# SECUREBRD_002.net
KiCad netlist of a schematic drawn in EAGLE
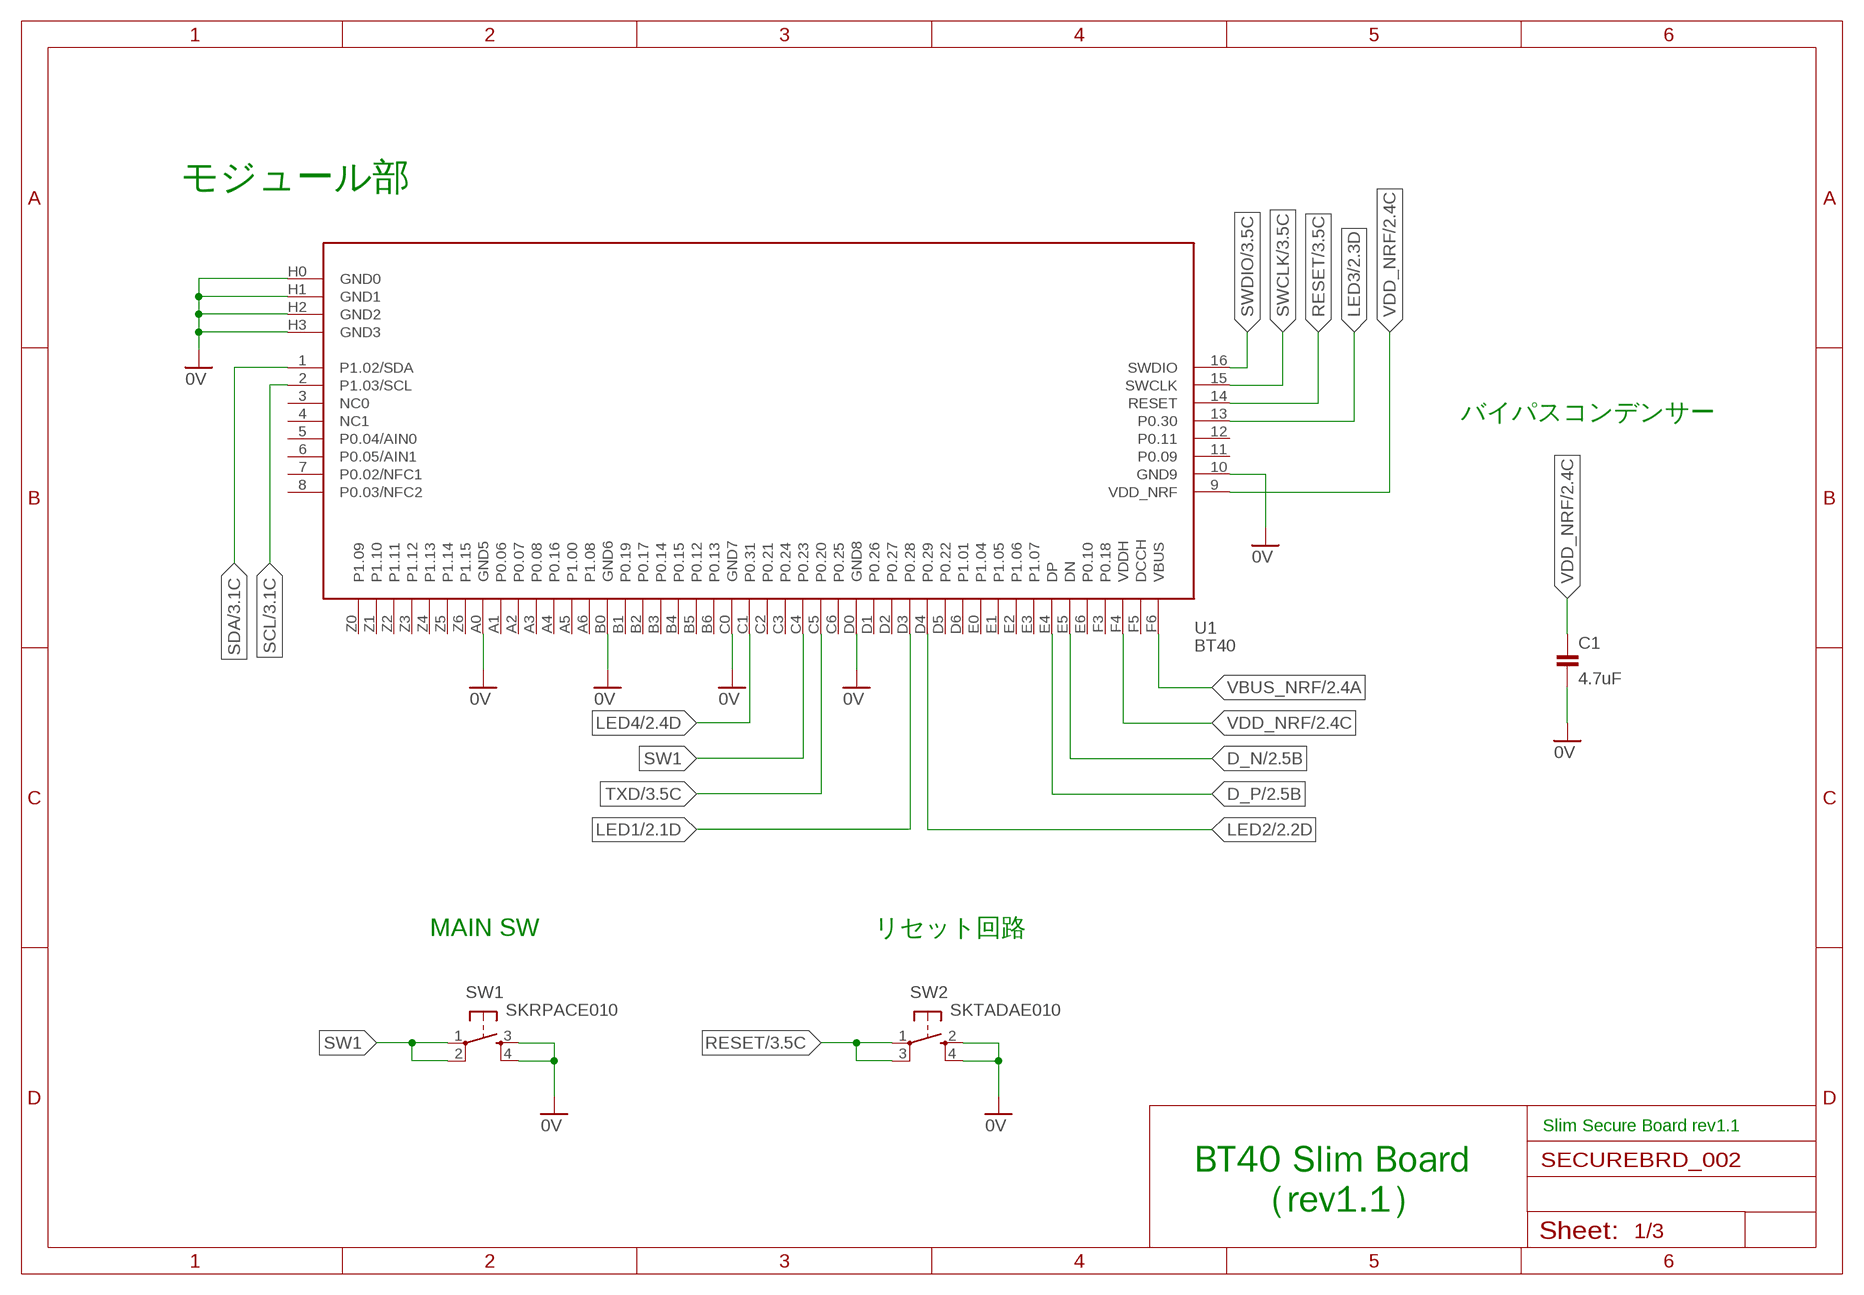
[diagram p0: schematic, sheet 1]
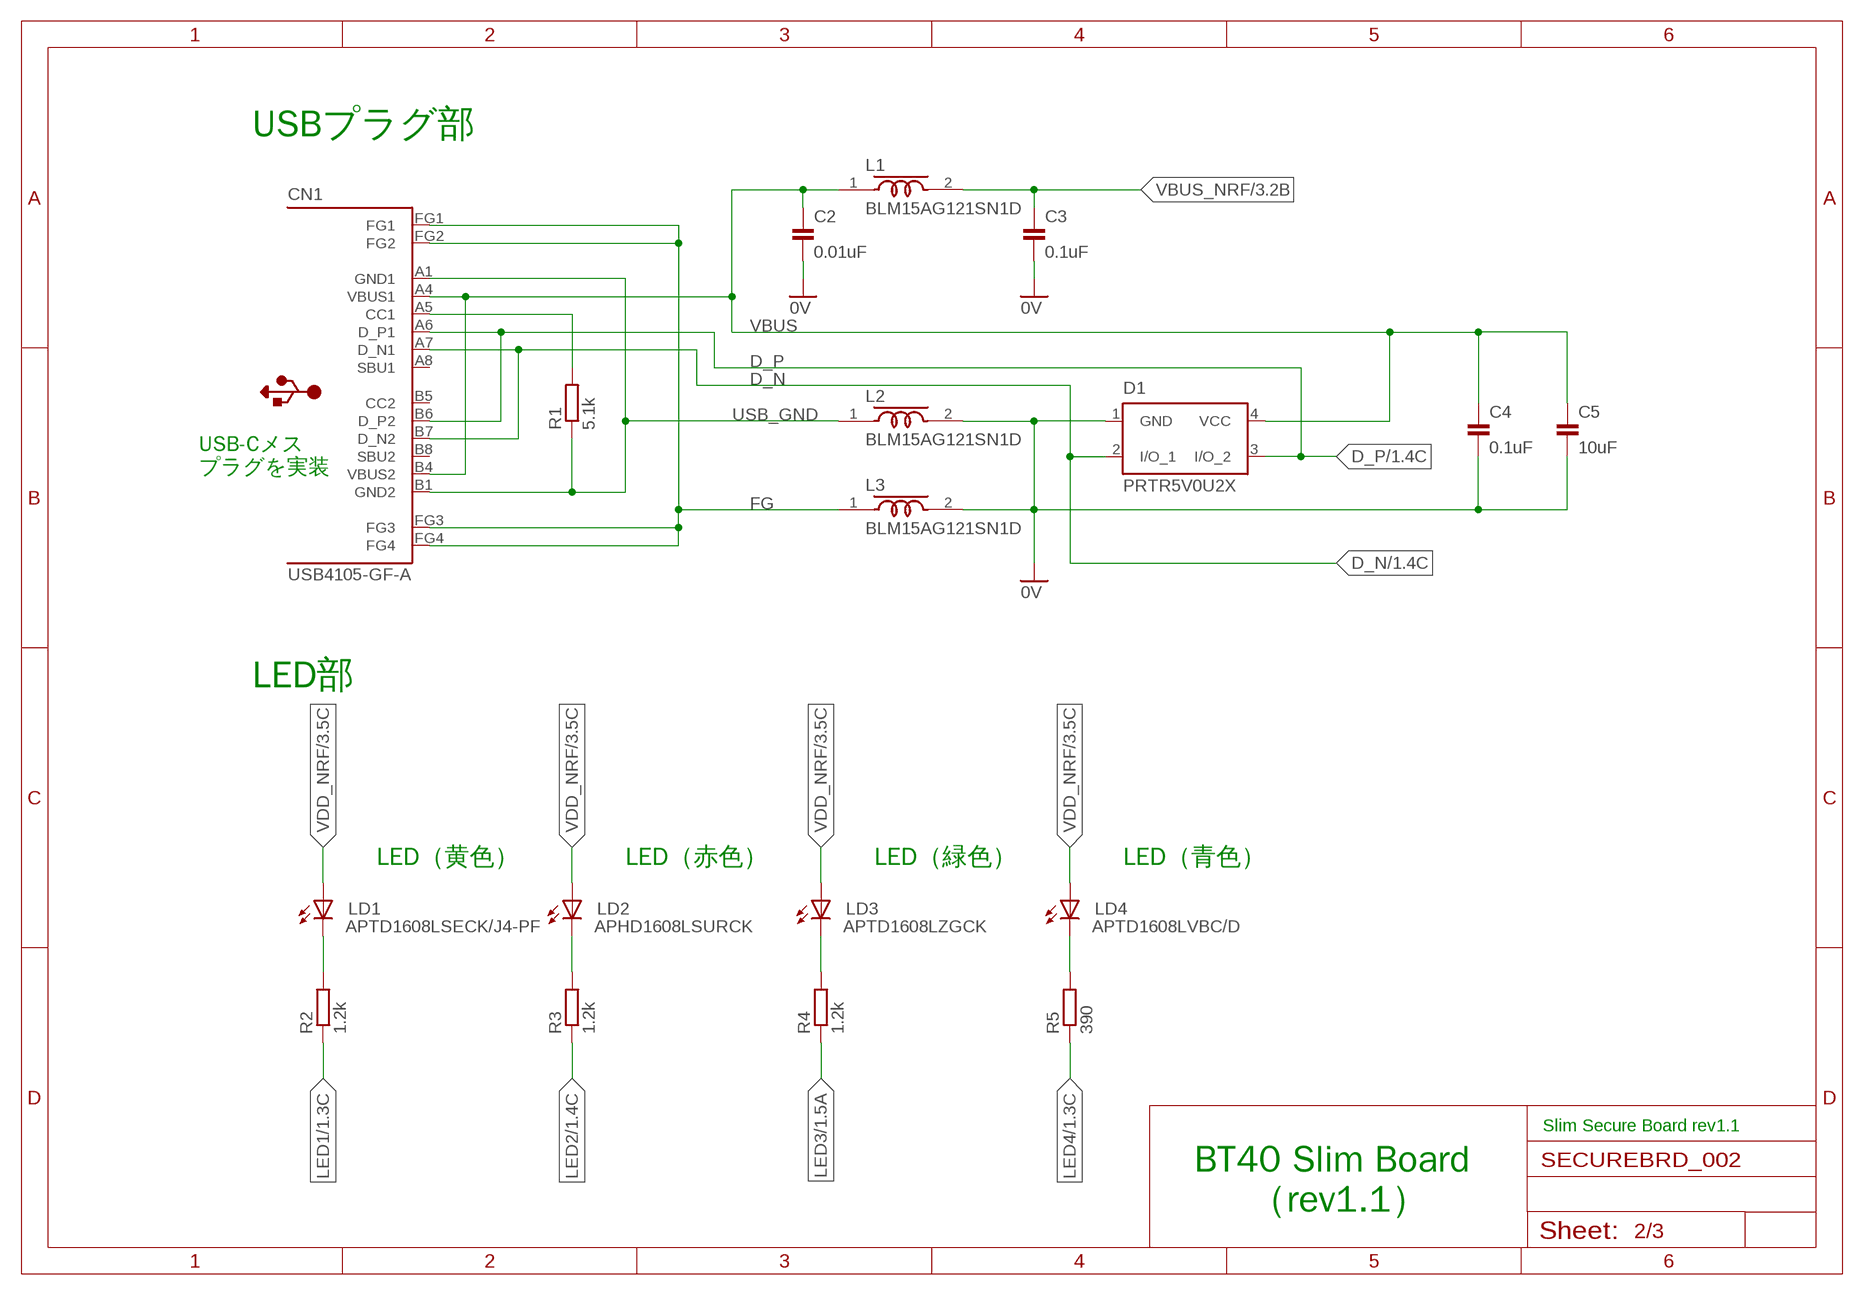
[diagram p1: schematic, sheet 2]
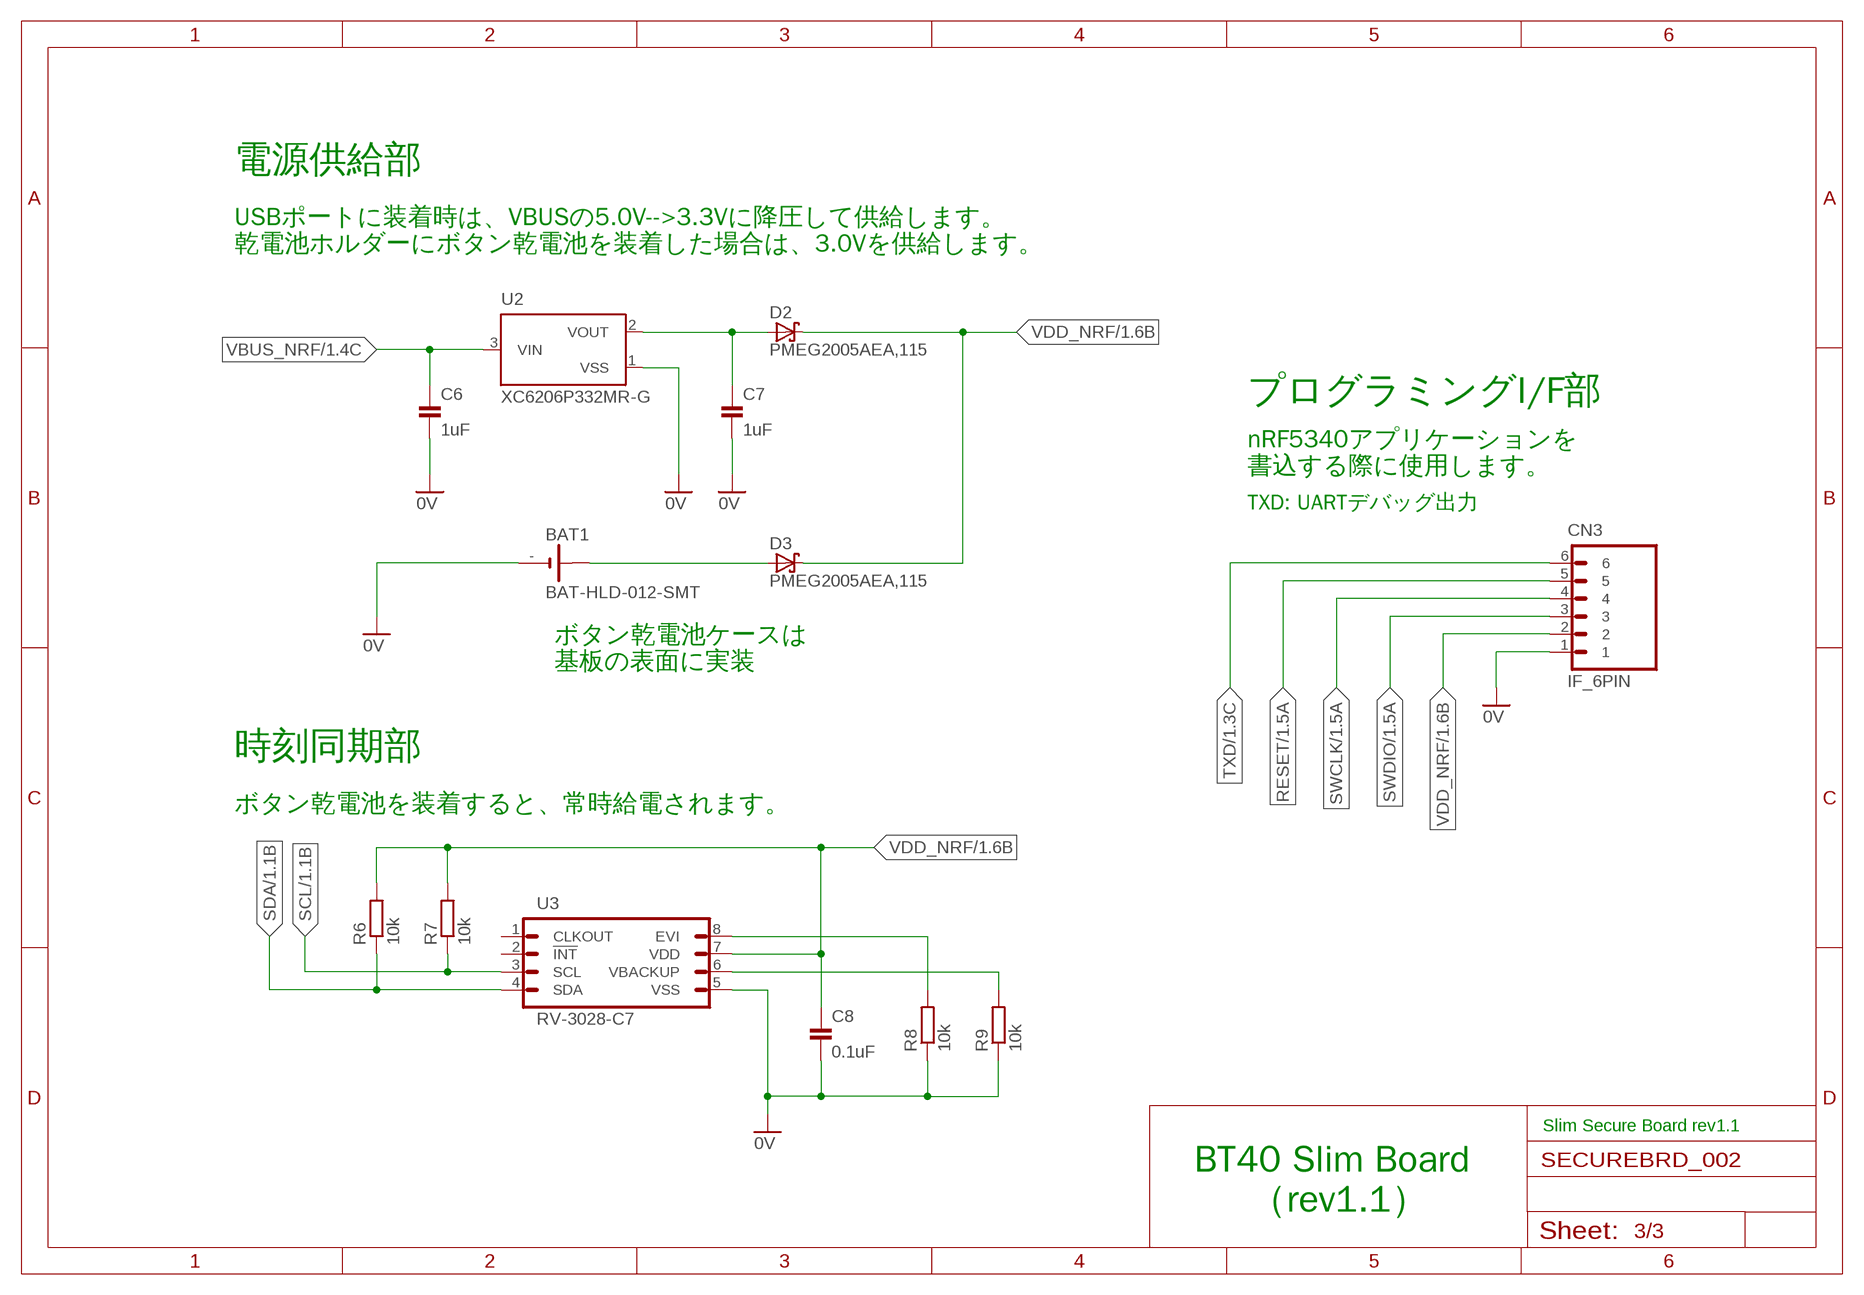
[diagram p2: schematic, sheet 3]

(export (version "E")
  (design (tool "Eeschema 10.0.6"))
  (components
    (comp (ref "C1")
      (value "4.7uF")
      (footprint "eagle-import:C0603K")
      (libsource (lib "eagle-import") (part "CAP_0603"))
    )
    (comp (ref "SW1")
      (value "SKRPACE010")
      (footprint "eagle-import:SKRPACE010")
      (libsource (lib "eagle-import") (part "SKRPACE010"))
    )
    (comp (ref "SW2")
      (value "SKTADAE010")
      (footprint "eagle-import:SKTADAE010")
      (libsource (lib "eagle-import") (part "SKTADAE010"))
    )
    (comp (ref "U1")
      (value "BT40")
      (footprint "eagle-import:BM40-B_1PRIMARY")
      (libsource (lib "eagle-import") (part "BT40"))
    )
    (comp (ref "C2")
      (value "0.01uF")
      (footprint "eagle-import:C0402K")
      (libsource (lib "eagle-import") (part "CAP_0402K"))
    )
    (comp (ref "C3")
      (value "0.1uF")
      (footprint "eagle-import:C0402K")
      (libsource (lib "eagle-import") (part "CAP_0402K"))
    )
    (comp (ref "C4")
      (value "0.1uF")
      (footprint "eagle-import:C0402K")
      (libsource (lib "eagle-import") (part "CAP_0402K"))
    )
    (comp (ref "C5")
      (value "10uF")
      (footprint "eagle-import:C0603K")
      (libsource (lib "eagle-import") (part "CAP_0603"))
    )
    (comp (ref "CN1")
      (value "USB4105-GF-A")
      (footprint "eagle-import:USB4105-GF-A")
      (libsource (lib "eagle-import") (part "USB4105-GF-A"))
    )
    (comp (ref "D1")
      (value "PRTR5V0U2X")
      (footprint "eagle-import:SOT143B")
      (libsource (lib "eagle-import") (part "PRTR5V0U2X"))
    )
    (comp (ref "L1")
      (value "BLM15AG121SN1D")
      (footprint "eagle-import:C0402K")
      (libsource (lib "eagle-import") (part "BLM15AG121SN1D"))
    )
    (comp (ref "L2")
      (value "BLM15AG121SN1D")
      (footprint "eagle-import:C0402K")
      (libsource (lib "eagle-import") (part "BLM15AG121SN1D"))
    )
    (comp (ref "L3")
      (value "BLM15AG121SN1D")
      (footprint "eagle-import:C0402K")
      (libsource (lib "eagle-import") (part "BLM15AG121SN1D"))
    )
    (comp (ref "LD1")
      (value "APTD1608LSECK/J4-PF")
      (footprint "eagle-import:APTD1608")
      (libsource (lib "eagle-import") (part "APTD1608LSECK/J4-PF"))
    )
    (comp (ref "LD2")
      (value "APHD1608LSURCK")
      (footprint "eagle-import:APTD1608")
      (libsource (lib "eagle-import") (part "APHD1608LSURCK"))
    )
    (comp (ref "LD3")
      (value "APTD1608LZGCK")
      (footprint "eagle-import:APTD1608")
      (libsource (lib "eagle-import") (part "APTD1608LZGCK"))
    )
    (comp (ref "LD4")
      (value "APTD1608LVBC/D")
      (footprint "eagle-import:APTD1608")
      (libsource (lib "eagle-import") (part "APTD1608LVBC/D"))
    )
    (comp (ref "R1")
      (value "5.1k")
      (footprint "eagle-import:R0402")
      (libsource (lib "eagle-import") (part "RESISTOR_0402"))
    )
    (comp (ref "R2")
      (value "1.2k")
      (footprint "eagle-import:R0402")
      (libsource (lib "eagle-import") (part "RESISTOR_0402"))
    )
    (comp (ref "R3")
      (value "1.2k")
      (footprint "eagle-import:R0402")
      (libsource (lib "eagle-import") (part "RESISTOR_0402"))
    )
    (comp (ref "R4")
      (value "1.2k")
      (footprint "eagle-import:R0402")
      (libsource (lib "eagle-import") (part "RESISTOR_0402"))
    )
    (comp (ref "R5")
      (value "390")
      (footprint "eagle-import:R0402")
      (libsource (lib "eagle-import") (part "RESISTOR_0402"))
    )
    (comp (ref "BAT1")
      (value "BAT-HLD-012-SMT")
      (footprint "eagle-import:BAT-HLD-012-SMT")
      (libsource (lib "eagle-import") (part "BAT-HLD-012-SMT"))
    )
    (comp (ref "C6")
      (value "1uF")
      (footprint "eagle-import:C0603K")
      (libsource (lib "eagle-import") (part "CAP_0603"))
    )
    (comp (ref "C7")
      (value "1uF")
      (footprint "eagle-import:C0603K")
      (libsource (lib "eagle-import") (part "CAP_0603"))
    )
    (comp (ref "C8")
      (value "0.1uF")
      (footprint "eagle-import:C0402K")
      (libsource (lib "eagle-import") (part "CAP_0402K"))
    )
    (comp (ref "CN3")
      (value "IF_6PIN")
      (footprint "eagle-import:HEADER_6PIN")
      (libsource (lib "eagle-import") (part "IF_6PIN"))
    )
    (comp (ref "D2")
      (value "PMEG2005AEA,115")
      (footprint "eagle-import:SOD323-W")
      (libsource (lib "eagle-import") (part "PMEG2005AEA,115"))
    )
    (comp (ref "D3")
      (value "PMEG2005AEA,115")
      (footprint "eagle-import:SOD323-W")
      (libsource (lib "eagle-import") (part "PMEG2005AEA,115"))
    )
    (comp (ref "R6")
      (value "10k")
      (footprint "eagle-import:R0402")
      (libsource (lib "eagle-import") (part "RESISTOR_0402"))
    )
    (comp (ref "R7")
      (value "10k")
      (footprint "eagle-import:R0402")
      (libsource (lib "eagle-import") (part "RESISTOR_0402"))
    )
    (comp (ref "R8")
      (value "10k")
      (footprint "eagle-import:R0402")
      (libsource (lib "eagle-import") (part "RESISTOR_0402"))
    )
    (comp (ref "R9")
      (value "10k")
      (footprint "eagle-import:R0402")
      (libsource (lib "eagle-import") (part "RESISTOR_0402"))
    )
    (comp (ref "U2")
      (value "XC6206P332MR-G")
      (footprint "eagle-import:SOT23")
      (libsource (lib "eagle-import") (part "XC6206P332MR-G"))
    )
    (comp (ref "U3")
      (value "RV-3028-C7")
      (footprint "eagle-import:SON-8")
      (libsource (lib "eagle-import") (part "RV-3028-C7"))
    )
  )
  (nets
    (net (code "1") (name "0V") (class "Default")
      (node (ref "BAT1") (pin "-") (pinfunction "-_-") (pintype "passive"))
      (node (ref "C1") (pin "2") (pinfunction "2_2") (pintype "passive"))
      (node (ref "C2") (pin "2") (pinfunction "2_2") (pintype "passive"))
      (node (ref "C3") (pin "2") (pinfunction "2_2") (pintype "passive"))
      (node (ref "C4") (pin "2") (pinfunction "2_2") (pintype "passive"))
      (node (ref "C5") (pin "2") (pinfunction "2_2") (pintype "passive"))
      (node (ref "C6") (pin "2") (pinfunction "2_2") (pintype "passive"))
      (node (ref "C7") (pin "2") (pinfunction "2_2") (pintype "passive"))
      (node (ref "C8") (pin "2") (pinfunction "2_2") (pintype "passive"))
      (node (ref "CN3") (pin "1") (pinfunction "1_1") (pintype "passive"))
      (node (ref "D1") (pin "1") (pinfunction "GND_1") (pintype "passive"))
      (node (ref "L2") (pin "2") (pinfunction "2_2") (pintype "passive"))
      (node (ref "L3") (pin "2") (pinfunction "2_2") (pintype "passive"))
      (node (ref "R8") (pin "1") (pinfunction "1_1") (pintype "passive"))
      (node (ref "R9") (pin "1") (pinfunction "1_1") (pintype "passive"))
      (node (ref "SW1") (pin "3") (pinfunction "S_3") (pintype "passive"))
      (node (ref "SW1") (pin "4") (pinfunction "S1_4") (pintype "passive"))
      (node (ref "SW2") (pin "2") (pinfunction "S_2") (pintype "passive"))
      (node (ref "SW2") (pin "4") (pinfunction "S1_4") (pintype "passive"))
      (node (ref "U1") (pin "10") (pinfunction "GND9_10") (pintype "passive"))
      (node (ref "U1") (pin "A0") (pinfunction "GND5_A0") (pintype "passive"))
      (node (ref "U1") (pin "B0") (pinfunction "GND6_B0") (pintype "passive"))
      (node (ref "U1") (pin "C0") (pinfunction "GND7_C0") (pintype "passive"))
      (node (ref "U1") (pin "D0") (pinfunction "GND8_D0") (pintype "passive"))
      (node (ref "U1") (pin "H0") (pinfunction "GND0_H0") (pintype "passive"))
      (node (ref "U1") (pin "H1") (pinfunction "GND1_H1") (pintype "passive"))
      (node (ref "U1") (pin "H2") (pinfunction "GND2_H2") (pintype "passive"))
      (node (ref "U1") (pin "H3") (pinfunction "GND3_H3") (pintype "passive"))
      (node (ref "U2") (pin "1") (pinfunction "VSS_1") (pintype "passive"))
      (node (ref "U3") (pin "5") (pinfunction "VSS_5") (pintype "passive"))
    )
    (net (code "2") (name "D_N") (class "Default")
      (node (ref "CN1") (pin "A7") (pinfunction "D_N1_A7") (pintype "bidirectional"))
      (node (ref "CN1") (pin "B7") (pinfunction "D_N2_B7") (pintype "bidirectional"))
      (node (ref "D1") (pin "2") (pinfunction "I/O_1_2") (pintype "bidirectional"))
      (node (ref "U1") (pin "E5") (pinfunction "DN_E5") (pintype "bidirectional"))
    )
    (net (code "3") (name "D_P") (class "Default")
      (node (ref "CN1") (pin "A6") (pinfunction "D_P1_A6") (pintype "bidirectional"))
      (node (ref "CN1") (pin "B6") (pinfunction "D_P2_B6") (pintype "bidirectional"))
      (node (ref "D1") (pin "3") (pinfunction "I/O_2_3") (pintype "bidirectional"))
      (node (ref "U1") (pin "E4") (pinfunction "DP_E4") (pintype "bidirectional"))
    )
    (net (code "4") (name "FG") (class "Default")
      (node (ref "CN1") (pin "FG1") (pinfunction "FG1_FG1") (pintype "passive"))
      (node (ref "CN1") (pin "FG2") (pinfunction "FG2_FG2") (pintype "bidirectional"))
      (node (ref "CN1") (pin "FG3") (pinfunction "FG3_FG3") (pintype "passive"))
      (node (ref "CN1") (pin "FG4") (pinfunction "FG4_FG4") (pintype "passive"))
      (node (ref "L3") (pin "1") (pinfunction "1_1") (pintype "passive"))
    )
    (net (code "5") (name "LED1") (class "Default")
      (node (ref "R2") (pin "1") (pinfunction "1_1") (pintype "passive"))
      (node (ref "U1") (pin "D3") (pinfunction "P0.28_D3") (pintype "bidirectional"))
    )
    (net (code "6") (name "LED2") (class "Default")
      (node (ref "R3") (pin "1") (pinfunction "1_1") (pintype "passive"))
      (node (ref "U1") (pin "D4") (pinfunction "P0.29_D4") (pintype "bidirectional"))
    )
    (net (code "7") (name "LED3") (class "Default")
      (node (ref "R4") (pin "1") (pinfunction "1_1") (pintype "passive"))
      (node (ref "U1") (pin "13") (pinfunction "P0.30_13") (pintype "bidirectional"))
    )
    (net (code "8") (name "LED4") (class "Default")
      (node (ref "R5") (pin "1") (pinfunction "1_1") (pintype "passive"))
      (node (ref "U1") (pin "C1") (pinfunction "P0.31_C1") (pintype "bidirectional"))
    )
    (net (code "9") (name "Net-(BAT1-+)") (class "Default")
      (node (ref "BAT1") (pin "+@2") (pinfunction "+_+@2") (pintype "passive"))
      (node (ref "D3") (pin "A") (pinfunction "A_A") (pintype "passive"))
    )
    (net (code "10") (name "Net-(CN1-CC1)") (class "Default")
      (node (ref "CN1") (pin "A5") (pinfunction "CC1_A5") (pintype "passive"))
      (node (ref "R1") (pin "2") (pinfunction "2_2") (pintype "passive"))
    )
    (net (code "11") (name "Net-(LD1-PadC)") (class "Default")
      (node (ref "LD1") (pin "C") (pinfunction "C_C") (pintype "passive"))
      (node (ref "R2") (pin "2") (pinfunction "2_2") (pintype "passive"))
    )
    (net (code "12") (name "Net-(LD2-PadC)") (class "Default")
      (node (ref "LD2") (pin "C") (pinfunction "C_C") (pintype "passive"))
      (node (ref "R3") (pin "2") (pinfunction "2_2") (pintype "passive"))
    )
    (net (code "13") (name "Net-(LD3-PadC)") (class "Default")
      (node (ref "LD3") (pin "C") (pinfunction "C_C") (pintype "passive"))
      (node (ref "R4") (pin "2") (pinfunction "2_2") (pintype "passive"))
    )
    (net (code "14") (name "Net-(LD4-PadC)") (class "Default")
      (node (ref "LD4") (pin "C") (pinfunction "C_C") (pintype "passive"))
      (node (ref "R5") (pin "2") (pinfunction "2_2") (pintype "passive"))
    )
    (net (code "15") (name "Net-(U2-VOUT)") (class "Default")
      (node (ref "C7") (pin "1") (pinfunction "1_1") (pintype "passive"))
      (node (ref "D2") (pin "A") (pinfunction "A_A") (pintype "passive"))
      (node (ref "U2") (pin "2") (pinfunction "VOUT_2") (pintype "passive"))
    )
    (net (code "16") (name "Net-(U3-EVI)") (class "Default")
      (node (ref "R8") (pin "2") (pinfunction "2_2") (pintype "passive"))
      (node (ref "U3") (pin "8") (pinfunction "EVI_8") (pintype "bidirectional"))
    )
    (net (code "17") (name "Net-(U3-VBACKUP)") (class "Default")
      (node (ref "R9") (pin "2") (pinfunction "2_2") (pintype "passive"))
      (node (ref "U3") (pin "6") (pinfunction "VBACKUP_6") (pintype "passive"))
    )
    (net (code "18") (name "RESET") (class "Default")
      (node (ref "CN3") (pin "5") (pinfunction "5_5") (pintype "passive"))
      (node (ref "SW2") (pin "1") (pinfunction "P_1") (pintype "passive"))
      (node (ref "SW2") (pin "3") (pinfunction "P1_3") (pintype "passive"))
      (node (ref "U1") (pin "14") (pinfunction "RESET_14") (pintype "bidirectional"))
    )
    (net (code "19") (name "SCL") (class "Default")
      (node (ref "R7") (pin "1") (pinfunction "1_1") (pintype "passive"))
      (node (ref "U1") (pin "2") (pinfunction "P1.03/SCL_2") (pintype "bidirectional"))
      (node (ref "U3") (pin "3") (pinfunction "SCL_3") (pintype "bidirectional"))
    )
    (net (code "20") (name "SDA") (class "Default")
      (node (ref "R6") (pin "1") (pinfunction "1_1") (pintype "passive"))
      (node (ref "U1") (pin "1") (pinfunction "P1.02/SDA_1") (pintype "bidirectional"))
      (node (ref "U3") (pin "4") (pinfunction "SDA_4") (pintype "bidirectional"))
    )
    (net (code "21") (name "SW1") (class "Default")
      (node (ref "SW1") (pin "1") (pinfunction "P_1") (pintype "passive"))
      (node (ref "SW1") (pin "2") (pinfunction "P1_2") (pintype "passive"))
      (node (ref "U1") (pin "C4") (pinfunction "P0.23_C4") (pintype "bidirectional"))
    )
    (net (code "22") (name "SWCLK") (class "Default")
      (node (ref "CN3") (pin "4") (pinfunction "4_4") (pintype "passive"))
      (node (ref "U1") (pin "15") (pinfunction "SWCLK_15") (pintype "bidirectional"))
    )
    (net (code "23") (name "SWDIO") (class "Default")
      (node (ref "CN3") (pin "3") (pinfunction "3_3") (pintype "passive"))
      (node (ref "U1") (pin "16") (pinfunction "SWDIO_16") (pintype "bidirectional"))
    )
    (net (code "24") (name "TXD") (class "Default")
      (node (ref "CN3") (pin "6") (pinfunction "6_6") (pintype "passive"))
      (node (ref "U1") (pin "C5") (pinfunction "P0.20_C5") (pintype "bidirectional"))
    )
    (net (code "25") (name "USB_GND") (class "Default")
      (node (ref "CN1") (pin "A1") (pinfunction "GND1_A1") (pintype "passive"))
      (node (ref "CN1") (pin "B1") (pinfunction "GND2_B1") (pintype "passive"))
      (node (ref "L2") (pin "1") (pinfunction "1_1") (pintype "passive"))
      (node (ref "R1") (pin "1") (pinfunction "1_1") (pintype "passive"))
    )
    (net (code "26") (name "VBUS") (class "Default")
      (node (ref "C2") (pin "1") (pinfunction "1_1") (pintype "passive"))
      (node (ref "C4") (pin "1") (pinfunction "1_1") (pintype "passive"))
      (node (ref "C5") (pin "1") (pinfunction "1_1") (pintype "passive"))
      (node (ref "CN1") (pin "A4") (pinfunction "VBUS1_A4") (pintype "passive"))
      (node (ref "CN1") (pin "B4") (pinfunction "VBUS2_B4") (pintype "passive"))
      (node (ref "D1") (pin "4") (pinfunction "VCC_4") (pintype "passive"))
      (node (ref "L1") (pin "1") (pinfunction "1_1") (pintype "passive"))
    )
    (net (code "27") (name "VBUS_NRF") (class "Default")
      (node (ref "C3") (pin "1") (pinfunction "1_1") (pintype "passive"))
      (node (ref "C6") (pin "1") (pinfunction "1_1") (pintype "passive"))
      (node (ref "L1") (pin "2") (pinfunction "2_2") (pintype "passive"))
      (node (ref "U1") (pin "F6") (pinfunction "VBUS_F6") (pintype "passive"))
      (node (ref "U2") (pin "3") (pinfunction "VIN_3") (pintype "passive"))
    )
    (net (code "28") (name "VDD_NRF") (class "Default")
      (node (ref "C1") (pin "1") (pinfunction "1_1") (pintype "passive"))
      (node (ref "C8") (pin "1") (pinfunction "1_1") (pintype "passive"))
      (node (ref "CN3") (pin "2") (pinfunction "2_2") (pintype "passive"))
      (node (ref "D2") (pin "C") (pinfunction "C_C") (pintype "passive"))
      (node (ref "D3") (pin "C") (pinfunction "C_C") (pintype "passive"))
      (node (ref "LD1") (pin "A") (pinfunction "A_A") (pintype "passive"))
      (node (ref "LD2") (pin "A") (pinfunction "A_A") (pintype "passive"))
      (node (ref "LD3") (pin "A") (pinfunction "A_A") (pintype "passive"))
      (node (ref "LD4") (pin "A") (pinfunction "A_A") (pintype "passive"))
      (node (ref "R6") (pin "2") (pinfunction "2_2") (pintype "passive"))
      (node (ref "R7") (pin "2") (pinfunction "2_2") (pintype "passive"))
      (node (ref "U1") (pin "9") (pinfunction "VDD_NRF_9") (pintype "passive"))
      (node (ref "U1") (pin "F4") (pinfunction "VDDH_F4") (pintype "passive"))
      (node (ref "U3") (pin "7") (pinfunction "VDD_7") (pintype "passive"))
    )
    (net (code "29") (name "unconnected-(CN1-CC2-PadB5)") (class "Default")
      (node (ref "CN1") (pin "B5") (pinfunction "CC2_B5") (pintype "passive"))
    )
    (net (code "30") (name "unconnected-(CN1-SBU1-PadA8)") (class "Default")
      (node (ref "CN1") (pin "A8") (pinfunction "SBU1_A8") (pintype "passive"))
    )
    (net (code "31") (name "unconnected-(CN1-SBU2-PadB8)") (class "Default")
      (node (ref "CN1") (pin "B8") (pinfunction "SBU2_B8") (pintype "passive"))
    )
    (net (code "32") (name "unconnected-(U1-DCCH-PadF5)") (class "Default")
      (node (ref "U1") (pin "F5") (pinfunction "DCCH_F5") (pintype "passive"))
    )
    (net (code "33") (name "unconnected-(U1-NC0-Pad3)") (class "Default")
      (node (ref "U1") (pin "3") (pinfunction "NC0_3") (pintype "no_connect"))
    )
    (net (code "34") (name "unconnected-(U1-NC1-Pad4)") (class "Default")
      (node (ref "U1") (pin "4") (pinfunction "NC1_4") (pintype "no_connect"))
    )
    (net (code "35") (name "unconnected-(U1-P0.02{slash}NFC1-Pad7)") (class "Default")
      (node (ref "U1") (pin "7") (pinfunction "P0.02/NFC1_7") (pintype "bidirectional"))
    )
    (net (code "36") (name "unconnected-(U1-P0.03{slash}NFC2-Pad8)") (class "Default")
      (node (ref "U1") (pin "8") (pinfunction "P0.03/NFC2_8") (pintype "bidirectional"))
    )
    (net (code "37") (name "unconnected-(U1-P0.04{slash}AIN0-Pad5)") (class "Default")
      (node (ref "U1") (pin "5") (pinfunction "P0.04/AIN0_5") (pintype "bidirectional"))
    )
    (net (code "38") (name "unconnected-(U1-P0.05{slash}AIN1-Pad6)") (class "Default")
      (node (ref "U1") (pin "6") (pinfunction "P0.05/AIN1_6") (pintype "bidirectional"))
    )
    (net (code "39") (name "unconnected-(U1-P0.06-PadA1)") (class "Default")
      (node (ref "U1") (pin "A1") (pinfunction "P0.06_A1") (pintype "bidirectional"))
    )
    (net (code "40") (name "unconnected-(U1-P0.07-PadA2)") (class "Default")
      (node (ref "U1") (pin "A2") (pinfunction "P0.07_A2") (pintype "bidirectional"))
    )
    (net (code "41") (name "unconnected-(U1-P0.08-PadA3)") (class "Default")
      (node (ref "U1") (pin "A3") (pinfunction "P0.08_A3") (pintype "bidirectional"))
    )
    (net (code "42") (name "unconnected-(U1-P0.09-Pad11)") (class "Default")
      (node (ref "U1") (pin "11") (pinfunction "P0.09_11") (pintype "bidirectional"))
    )
    (net (code "43") (name "unconnected-(U1-P0.10-PadE6)") (class "Default")
      (node (ref "U1") (pin "E6") (pinfunction "P0.10_E6") (pintype "bidirectional"))
    )
    (net (code "44") (name "unconnected-(U1-P0.11-Pad12)") (class "Default")
      (node (ref "U1") (pin "12") (pinfunction "P0.11_12") (pintype "bidirectional"))
    )
    (net (code "45") (name "unconnected-(U1-P0.12-PadB5)") (class "Default")
      (node (ref "U1") (pin "B5") (pinfunction "P0.12_B5") (pintype "bidirectional"))
    )
    (net (code "46") (name "unconnected-(U1-P0.13-PadB6)") (class "Default")
      (node (ref "U1") (pin "B6") (pinfunction "P0.13_B6") (pintype "bidirectional"))
    )
    (net (code "47") (name "unconnected-(U1-P0.14-PadB3)") (class "Default")
      (node (ref "U1") (pin "B3") (pinfunction "P0.14_B3") (pintype "bidirectional"))
    )
    (net (code "48") (name "unconnected-(U1-P0.15-PadB4)") (class "Default")
      (node (ref "U1") (pin "B4") (pinfunction "P0.15_B4") (pintype "bidirectional"))
    )
    (net (code "49") (name "unconnected-(U1-P0.16-PadA4)") (class "Default")
      (node (ref "U1") (pin "A4") (pinfunction "P0.16_A4") (pintype "bidirectional"))
    )
    (net (code "50") (name "unconnected-(U1-P0.17-PadB2)") (class "Default")
      (node (ref "U1") (pin "B2") (pinfunction "P0.17_B2") (pintype "bidirectional"))
    )
    (net (code "51") (name "unconnected-(U1-P0.18-PadF3)") (class "Default")
      (node (ref "U1") (pin "F3") (pinfunction "P0.18_F3") (pintype "bidirectional"))
    )
    (net (code "52") (name "unconnected-(U1-P0.19-PadB1)") (class "Default")
      (node (ref "U1") (pin "B1") (pinfunction "P0.19_B1") (pintype "bidirectional"))
    )
    (net (code "53") (name "unconnected-(U1-P0.21-PadC2)") (class "Default")
      (node (ref "U1") (pin "C2") (pinfunction "P0.21_C2") (pintype "bidirectional"))
    )
    (net (code "54") (name "unconnected-(U1-P0.22-PadD5)") (class "Default")
      (node (ref "U1") (pin "D5") (pinfunction "P0.22_D5") (pintype "bidirectional"))
    )
    (net (code "55") (name "unconnected-(U1-P0.24-PadC3)") (class "Default")
      (node (ref "U1") (pin "C3") (pinfunction "P0.24_C3") (pintype "bidirectional"))
    )
    (net (code "56") (name "unconnected-(U1-P0.25-PadC6)") (class "Default")
      (node (ref "U1") (pin "C6") (pinfunction "P0.25_C6") (pintype "bidirectional"))
    )
    (net (code "57") (name "unconnected-(U1-P0.26-PadD1)") (class "Default")
      (node (ref "U1") (pin "D1") (pinfunction "P0.26_D1") (pintype "bidirectional"))
    )
    (net (code "58") (name "unconnected-(U1-P0.27-PadD2)") (class "Default")
      (node (ref "U1") (pin "D2") (pinfunction "P0.27_D2") (pintype "bidirectional"))
    )
    (net (code "59") (name "unconnected-(U1-P1.00-PadA5)") (class "Default")
      (node (ref "U1") (pin "A5") (pinfunction "P1.00_A5") (pintype "bidirectional"))
    )
    (net (code "60") (name "unconnected-(U1-P1.01-PadD6)") (class "Default")
      (node (ref "U1") (pin "D6") (pinfunction "P1.01_D6") (pintype "bidirectional"))
    )
    (net (code "61") (name "unconnected-(U1-P1.04-PadE0)") (class "Default")
      (node (ref "U1") (pin "E0") (pinfunction "P1.04_E0") (pintype "bidirectional"))
    )
    (net (code "62") (name "unconnected-(U1-P1.05-PadE1)") (class "Default")
      (node (ref "U1") (pin "E1") (pinfunction "P1.05_E1") (pintype "bidirectional"))
    )
    (net (code "63") (name "unconnected-(U1-P1.06-PadE2)") (class "Default")
      (node (ref "U1") (pin "E2") (pinfunction "P1.06_E2") (pintype "bidirectional"))
    )
    (net (code "64") (name "unconnected-(U1-P1.07-PadE3)") (class "Default")
      (node (ref "U1") (pin "E3") (pinfunction "P1.07_E3") (pintype "bidirectional"))
    )
    (net (code "65") (name "unconnected-(U1-P1.08-PadA6)") (class "Default")
      (node (ref "U1") (pin "A6") (pinfunction "P1.08_A6") (pintype "bidirectional"))
    )
    (net (code "66") (name "unconnected-(U1-P1.09-PadZ0)") (class "Default")
      (node (ref "U1") (pin "Z0") (pinfunction "P1.09_Z0") (pintype "bidirectional"))
    )
    (net (code "67") (name "unconnected-(U1-P1.10-PadZ1)") (class "Default")
      (node (ref "U1") (pin "Z1") (pinfunction "P1.10_Z1") (pintype "bidirectional"))
    )
    (net (code "68") (name "unconnected-(U1-P1.11-PadZ2)") (class "Default")
      (node (ref "U1") (pin "Z2") (pinfunction "P1.11_Z2") (pintype "bidirectional"))
    )
    (net (code "69") (name "unconnected-(U1-P1.12-PadZ3)") (class "Default")
      (node (ref "U1") (pin "Z3") (pinfunction "P1.12_Z3") (pintype "bidirectional"))
    )
    (net (code "70") (name "unconnected-(U1-P1.13-PadZ4)") (class "Default")
      (node (ref "U1") (pin "Z4") (pinfunction "P1.13_Z4") (pintype "bidirectional"))
    )
    (net (code "71") (name "unconnected-(U1-P1.14-PadZ5)") (class "Default")
      (node (ref "U1") (pin "Z5") (pinfunction "P1.14_Z5") (pintype "bidirectional"))
    )
    (net (code "72") (name "unconnected-(U1-P1.15-PadZ6)") (class "Default")
      (node (ref "U1") (pin "Z6") (pinfunction "P1.15_Z6") (pintype "bidirectional"))
    )
    (net (code "73") (name "unconnected-(U3-CLKOUT-Pad1)") (class "Default")
      (node (ref "U3") (pin "1") (pinfunction "CLKOUT_1") (pintype "bidirectional"))
    )
    (net (code "74") (name "unconnected-(U3-~{INT}-Pad2)") (class "Default")
      (node (ref "U3") (pin "2") (pinfunction "~{INT}_2") (pintype "bidirectional"))
    )
  )
)
